# DM2080_Connector_A.net
KiCad netlist of a schematic drawn in Altium Designer
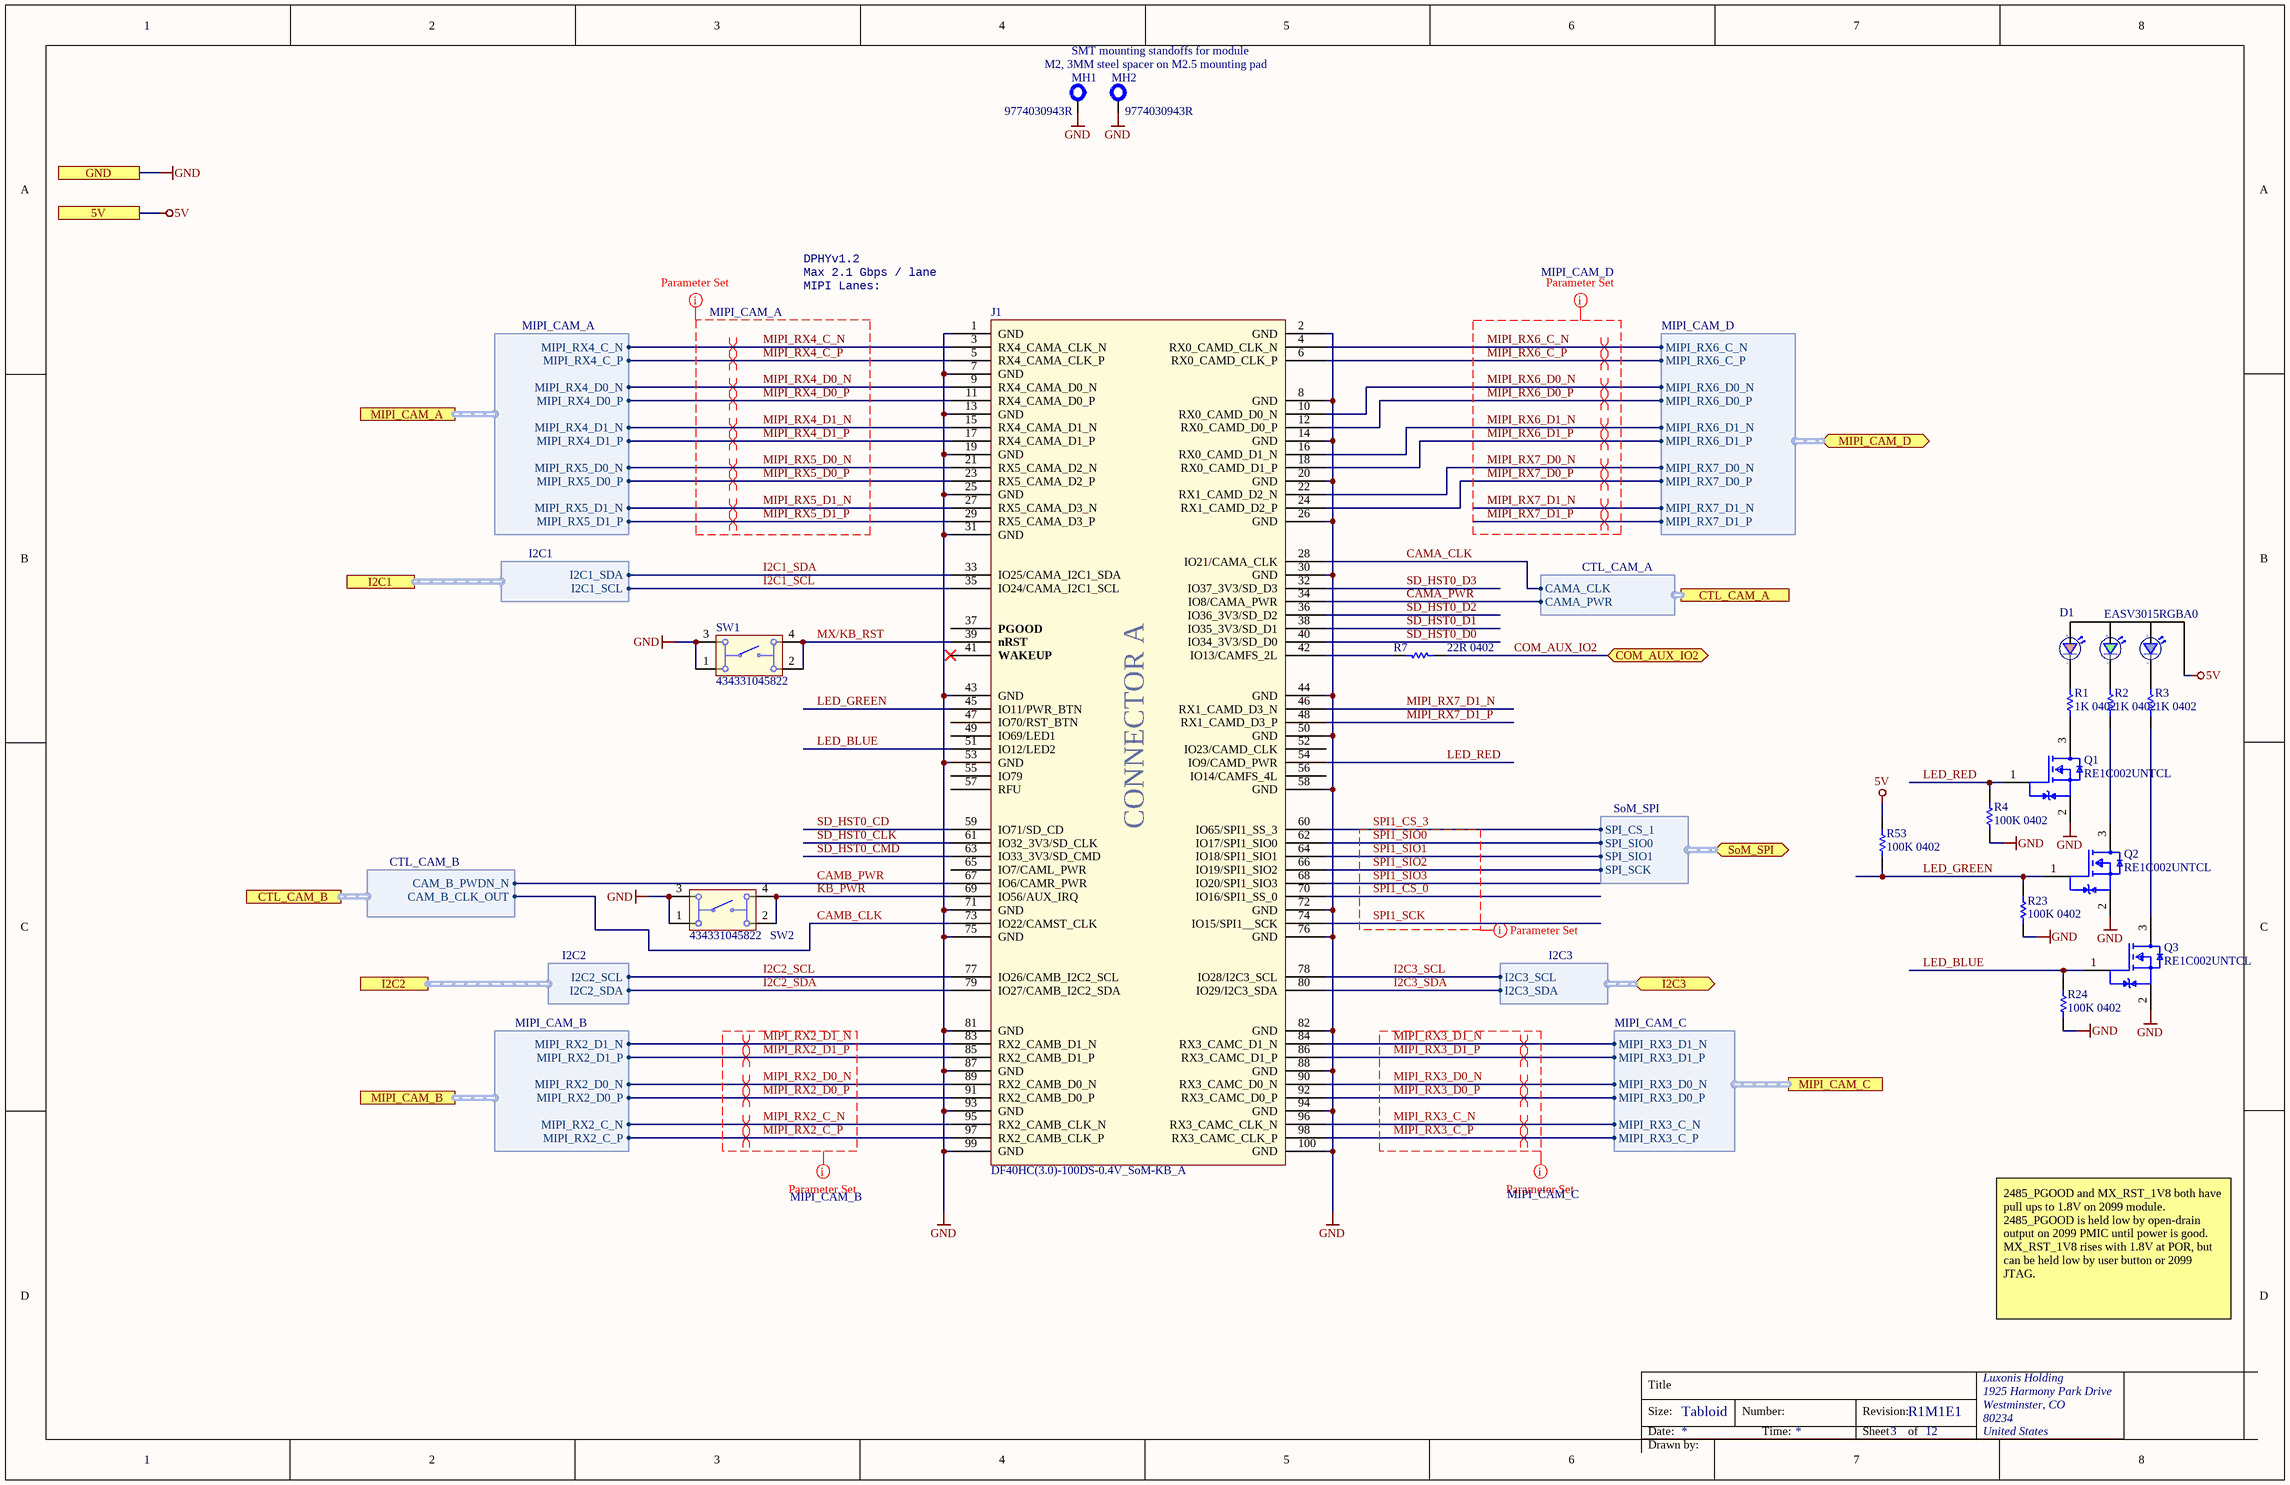
[diagram p0: DM2080_Connector_A.SchDoc]

(export (version "E")
  (design (tool "Eeschema 10.0.6"))
  (components
    (comp (ref "D1")
      (value "EASV3015RGBA0")
      (footprint "EASV3015RGBA0")
      (description "LED Tri-Color Blue/Green/Red 468nm/518nm/632nm 4-Pin SMD")
      (libsource (lib "NG2391C-HM") (part "EASV3015RGBA0"))
    )
    (comp (ref "J1")
      (value "DF40HC(3.0)-100DS-0.4V_SoM-KB_A")
      (footprint "CON_A_SoM-Pro-KB_DF40HC-3.0-100DS-0.4V_minpad")
      (description "OAK-SoM-Pro-S3 base board conn. A")
      (libsource (lib "Luxonis LLC") (part "DF40HC(3.0)-100DS-0.4V_SoM-KB_A"))
    )
    (comp (ref "MH1")
      (value "9774030943R")
      (footprint "9774030943R")
      (description "Spacers/Standoffs")
      (libsource (lib "Luxonis LLC") (part "9774030943R"))
    )
    (comp (ref "MH2")
      (value "9774030943R")
      (footprint "9774030943R")
      (description "Spacers/Standoffs")
      (libsource (lib "Luxonis LLC") (part "9774030943R"))
    )
    (comp (ref "Q1")
      (value "RE1C002UNTCL")
      (footprint "LuxonisMaster:RE1C002UNTCL")
      (description "MOSFET N-CH 20V 0.2A EMT3")
      (libsource (lib "LuxonisMaster") (part "RE1C002UNTCL"))
    )
    (comp (ref "Q2")
      (value "RE1C002UNTCL")
      (footprint "LuxonisMaster:RE1C002UNTCL")
      (description "MOSFET N-CH 20V 0.2A EMT3")
      (libsource (lib "LuxonisMaster") (part "RE1C002UNTCL"))
    )
    (comp (ref "Q3")
      (value "RE1C002UNTCL")
      (footprint "LuxonisMaster:RE1C002UNTCL")
      (description "MOSFET N-CH 20V 0.2A EMT3")
      (libsource (lib "LuxonisMaster") (part "RE1C002UNTCL"))
    )
    (comp (ref "R1")
      (value "1K 0402")
      (footprint "RES_Altium_Vault_Generic:RESC0402(1005)_L")
      (description "RES SMD 1K OHM 1% 1/16W 0402")
      (fields (field (name "TOLERANCE") "1%"))
      (libsource (lib "LuxonisMaster") (part "RC0402FR-071KL"))
    )
    (comp (ref "R2")
      (value "1K 0402")
      (footprint "RES_Altium_Vault_Generic:RESC0402(1005)_L")
      (description "RES SMD 1K OHM 1% 1/16W 0402")
      (fields (field (name "TOLERANCE") "1%"))
      (libsource (lib "LuxonisMaster") (part "RC0402FR-071KL"))
    )
    (comp (ref "R3")
      (value "1K 0402")
      (footprint "RES_Altium_Vault_Generic:RESC0402(1005)_L")
      (description "RES SMD 1K OHM 1% 1/16W 0402")
      (fields (field (name "TOLERANCE") "1%"))
      (libsource (lib "LuxonisMaster") (part "RC0402FR-071KL"))
    )
    (comp (ref "R4")
      (value "100K 0402")
      (footprint "RESC0402(1005)_L")
      (description "RES SMD 100K OHM 1% 1/16W 0402")
      (fields (field (name "TOLERANCE") "1%"))
      (libsource (lib "Luxonis LLC") (part "CR0402-FX-2492GLF"))
    )
    (comp (ref "R7")
      (value "22R 0402")
      (footprint "RES_Altium_Vault_Generic:RESC0402(1005)_L")
      (description "RES SMD 22 OHM 1% 1/16W 0402")
      (fields (field (name "TOLERANCE") "1%"))
      (libsource (lib "BW2098POE") (part "RC0402FR-0722RL"))
    )
    (comp (ref "R23")
      (value "100K 0402")
      (footprint "RESC0402(1005)_L")
      (description "RES SMD 100K OHM 1% 1/16W 0402")
      (fields (field (name "TOLERANCE") "1%"))
      (libsource (lib "Luxonis LLC") (part "CR0402-FX-2492GLF"))
    )
    (comp (ref "R24")
      (value "100K 0402")
      (footprint "RESC0402(1005)_L")
      (description "RES SMD 100K OHM 1% 1/16W 0402")
      (fields (field (name "TOLERANCE") "1%"))
      (libsource (lib "Luxonis LLC") (part "CR0402-FX-2492GLF"))
    )
    (comp (ref "R53")
      (value "100K 0402")
      (footprint "RESC0402(1005)_L")
      (description "RES SMD 100K OHM 1% 1/16W 0402")
      (fields (field (name "TOLERANCE") "1%"))
      (libsource (lib "Luxonis LLC") (part "CR0402-FX-2492GLF"))
    )
    (comp (ref "SW1")
      (value "434331045822")
      (footprint "434331045822")
      (libsource (lib "Luxonis LLC") (part "WE-TACT-SW-4"))
    )
    (comp (ref "SW2")
      (value "434331045822")
      (footprint "434331045822")
      (libsource (lib "Luxonis LLC") (part "WE-TACT-SW-4"))
    )
  )
  (nets
    (net (code "11") (name "/CAMA_CLK") (class "Default")
      (node (ref "J1") (pin "28") (pinfunction "IO21/CAMA_CLK_28") (pintype "passive"))
    )
    (net (code "12") (name "/CAMA_PWR") (class "Default")
      (node (ref "J1") (pin "34") (pinfunction "IO8/CAMA_PWR_34") (pintype "passive"))
    )
    (net (code "13") (name "/CAMB_CLK") (class "Default")
      (node (ref "J1") (pin "73") (pinfunction "IO22/CAMST_CLK_73") (pintype "passive"))
    )
    (net (code "14") (name "/CAMB_PWR") (class "Default")
      (node (ref "J1") (pin "67") (pinfunction "IO6/CAMR_PWR_67") (pintype "passive"))
    )
    (net (code "15") (name "/COM_AUX_IO2") (class "Default")
      (node (ref "R7") (pin "1") (pinfunction "1_1") (pintype "passive"))
    )
    (net (code "16") (name "/I2C1_SCL") (class "Default")
      (node (ref "J1") (pin "35") (pinfunction "IO24/CAMA_I2C1_SCL_35") (pintype "passive"))
    )
    (net (code "17") (name "/I2C1_SDA") (class "Default")
      (node (ref "J1") (pin "33") (pinfunction "IO25/CAMA_I2C1_SDA_33") (pintype "passive"))
    )
    (net (code "18") (name "/I2C2_SCL") (class "Default")
      (node (ref "J1") (pin "77") (pinfunction "IO26/CAMB_I2C2_SCL_77") (pintype "passive"))
    )
    (net (code "19") (name "/I2C2_SDA") (class "Default")
      (node (ref "J1") (pin "79") (pinfunction "IO27/CAMB_I2C2_SDA_79") (pintype "passive"))
    )
    (net (code "20") (name "/I2C3_SCL") (class "Default")
      (node (ref "J1") (pin "78") (pinfunction "IO28/I2C3_SCL_78") (pintype "passive"))
    )
    (net (code "21") (name "/I2C3_SDA") (class "Default")
      (node (ref "J1") (pin "80") (pinfunction "IO29/I2C3_SDA_80") (pintype "passive"))
    )
    (net (code "22") (name "/KB_PWR") (class "Default")
      (node (ref "J1") (pin "69") (pinfunction "IO56/AUX_IRQ_69") (pintype "passive"))
      (node (ref "SW2") (pin "2") (pinfunction "2_2") (pintype "passive"))
      (node (ref "SW2") (pin "4") (pinfunction "4_4") (pintype "passive"))
    )
    (net (code "23") (name "/LED_BLUE") (class "Default")
      (node (ref "J1") (pin "51") (pinfunction "IO12/LED2_51") (pintype "passive"))
      (node (ref "Q3") (pin "1") (pinfunction "Gate_1") (pintype "passive"))
      (node (ref "R24") (pin "1") (pinfunction "1_1") (pintype "passive"))
    )
    (net (code "24") (name "/LED_GREEN") (class "Default")
      (node (ref "J1") (pin "45") (pinfunction "IO11/PWR_BTN_45") (pintype "passive"))
      (node (ref "Q2") (pin "1") (pinfunction "Gate_1") (pintype "passive"))
      (node (ref "R23") (pin "1") (pinfunction "1_1") (pintype "passive"))
      (node (ref "R53") (pin "2") (pinfunction "2_2") (pintype "passive"))
    )
    (net (code "25") (name "/LED_RED") (class "Default")
      (node (ref "J1") (pin "54") (pinfunction "IO9/CAMD_PWR_54") (pintype "passive"))
      (node (ref "Q1") (pin "1") (pinfunction "Gate_1") (pintype "passive"))
      (node (ref "R4") (pin "1") (pinfunction "1_1") (pintype "passive"))
    )
    (net (code "26") (name "/MIPI_RX2_C_N") (class "Default")
      (node (ref "J1") (pin "95") (pinfunction "RX2_CAMB_CLK_N_95") (pintype "passive"))
    )
    (net (code "27") (name "/MIPI_RX2_C_P") (class "Default")
      (node (ref "J1") (pin "97") (pinfunction "RX2_CAMB_CLK_P_97") (pintype "passive"))
    )
    (net (code "28") (name "/MIPI_RX2_D0_N") (class "Default")
      (node (ref "J1") (pin "89") (pinfunction "RX2_CAMB_D0_N_89") (pintype "passive"))
    )
    (net (code "29") (name "/MIPI_RX2_D0_P") (class "Default")
      (node (ref "J1") (pin "91") (pinfunction "RX2_CAMB_D0_P_91") (pintype "passive"))
    )
    (net (code "30") (name "/MIPI_RX2_D1_N") (class "Default")
      (node (ref "J1") (pin "83") (pinfunction "RX2_CAMB_D1_N_83") (pintype "passive"))
    )
    (net (code "31") (name "/MIPI_RX2_D1_P") (class "Default")
      (node (ref "J1") (pin "85") (pinfunction "RX2_CAMB_D1_P_85") (pintype "passive"))
    )
    (net (code "32") (name "/MIPI_RX3_C_N") (class "Default")
      (node (ref "J1") (pin "96") (pinfunction "RX3_CAMC_CLK_N_96") (pintype "passive"))
    )
    (net (code "33") (name "/MIPI_RX3_C_P") (class "Default")
      (node (ref "J1") (pin "98") (pinfunction "RX3_CAMC_CLK_P_98") (pintype "passive"))
    )
    (net (code "34") (name "/MIPI_RX3_D0_N") (class "Default")
      (node (ref "J1") (pin "90") (pinfunction "RX3_CAMC_D0_N_90") (pintype "passive"))
    )
    (net (code "35") (name "/MIPI_RX3_D0_P") (class "Default")
      (node (ref "J1") (pin "92") (pinfunction "RX3_CAMC_D0_P_92") (pintype "passive"))
    )
    (net (code "36") (name "/MIPI_RX3_D1_N") (class "Default")
      (node (ref "J1") (pin "84") (pinfunction "RX3_CAMC_D1_N_84") (pintype "passive"))
    )
    (net (code "37") (name "/MIPI_RX3_D1_P") (class "Default")
      (node (ref "J1") (pin "86") (pinfunction "RX3_CAMC_D1_P_86") (pintype "passive"))
    )
    (net (code "38") (name "/MIPI_RX4_C_N") (class "Default")
      (node (ref "J1") (pin "3") (pinfunction "RX4_CAMA_CLK_N_3") (pintype "passive"))
    )
    (net (code "39") (name "/MIPI_RX4_C_P") (class "Default")
      (node (ref "J1") (pin "5") (pinfunction "RX4_CAMA_CLK_P_5") (pintype "passive"))
    )
    (net (code "40") (name "/MIPI_RX4_D0_N") (class "Default")
      (node (ref "J1") (pin "9") (pinfunction "RX4_CAMA_D0_N_9") (pintype "passive"))
    )
    (net (code "41") (name "/MIPI_RX4_D0_P") (class "Default")
      (node (ref "J1") (pin "11") (pinfunction "RX4_CAMA_D0_P_11") (pintype "passive"))
    )
    (net (code "42") (name "/MIPI_RX4_D1_N") (class "Default")
      (node (ref "J1") (pin "15") (pinfunction "RX4_CAMA_D1_N_15") (pintype "passive"))
    )
    (net (code "43") (name "/MIPI_RX4_D1_P") (class "Default")
      (node (ref "J1") (pin "17") (pinfunction "RX4_CAMA_D1_P_17") (pintype "passive"))
    )
    (net (code "44") (name "/MIPI_RX5_D0_N") (class "Default")
      (node (ref "J1") (pin "21") (pinfunction "RX5_CAMA_D2_N_21") (pintype "passive"))
    )
    (net (code "45") (name "/MIPI_RX5_D0_P") (class "Default")
      (node (ref "J1") (pin "23") (pinfunction "RX5_CAMA_D2_P_23") (pintype "passive"))
    )
    (net (code "46") (name "/MIPI_RX5_D1_N") (class "Default")
      (node (ref "J1") (pin "27") (pinfunction "RX5_CAMA_D3_N_27") (pintype "passive"))
    )
    (net (code "47") (name "/MIPI_RX5_D1_P") (class "Default")
      (node (ref "J1") (pin "29") (pinfunction "RX5_CAMA_D3_P_29") (pintype "passive"))
    )
    (net (code "48") (name "/MIPI_RX6_C_N") (class "Default")
      (node (ref "J1") (pin "4") (pinfunction "RX0_CAMD_CLK_N_4") (pintype "passive"))
    )
    (net (code "49") (name "/MIPI_RX6_C_P") (class "Default")
      (node (ref "J1") (pin "6") (pinfunction "RX0_CAMD_CLK_P_6") (pintype "passive"))
    )
    (net (code "50") (name "/MIPI_RX6_D0_N") (class "Default")
      (node (ref "J1") (pin "10") (pinfunction "RX0_CAMD_D0_N_10") (pintype "passive"))
    )
    (net (code "51") (name "/MIPI_RX6_D0_P") (class "Default")
      (node (ref "J1") (pin "12") (pinfunction "RX0_CAMD_D0_P_12") (pintype "passive"))
    )
    (net (code "52") (name "/MIPI_RX6_D1_N") (class "Default")
      (node (ref "J1") (pin "16") (pinfunction "RX0_CAMD_D1_N_16") (pintype "passive"))
    )
    (net (code "53") (name "/MIPI_RX6_D1_P") (class "Default")
      (node (ref "J1") (pin "18") (pinfunction "RX0_CAMD_D1_P_18") (pintype "passive"))
    )
    (net (code "54") (name "/MIPI_RX7_D0_N") (class "Default")
      (node (ref "J1") (pin "22") (pinfunction "RX1_CAMD_D2_N_22") (pintype "passive"))
    )
    (net (code "55") (name "/MIPI_RX7_D0_P") (class "Default")
      (node (ref "J1") (pin "24") (pinfunction "RX1_CAMD_D2_P_24") (pintype "passive"))
    )
    (net (code "56") (name "/MIPI_RX7_D1_N") (class "Default")
      (node (ref "J1") (pin "46") (pinfunction "RX1_CAMD_D3_N_46") (pintype "passive"))
    )
    (net (code "57") (name "/MIPI_RX7_D1_P") (class "Default")
      (node (ref "J1") (pin "48") (pinfunction "RX1_CAMD_D3_P_48") (pintype "passive"))
    )
    (net (code "58") (name "/MX{slash}KB_RST") (class "Default")
      (node (ref "J1") (pin "39") (pinfunction "nRST_39") (pintype "passive"))
      (node (ref "SW1") (pin "2") (pinfunction "2_2") (pintype "passive"))
      (node (ref "SW1") (pin "4") (pinfunction "4_4") (pintype "passive"))
    )
    (net (code "59") (name "/SD_HST0_CD") (class "Default")
      (node (ref "J1") (pin "59") (pinfunction "IO71/SD_CD_59") (pintype "passive"))
    )
    (net (code "60") (name "/SD_HST0_CLK") (class "Default")
      (node (ref "J1") (pin "61") (pinfunction "IO32_3V3/SD_CLK_61") (pintype "passive"))
    )
    (net (code "61") (name "/SD_HST0_CMD") (class "Default")
      (node (ref "J1") (pin "63") (pinfunction "IO33_3V3/SD_CMD_63") (pintype "passive"))
    )
    (net (code "62") (name "/SD_HST0_D0") (class "Default")
      (node (ref "J1") (pin "40") (pinfunction "IO34_3V3/SD_D0_40") (pintype "passive"))
    )
    (net (code "63") (name "/SD_HST0_D1") (class "Default")
      (node (ref "J1") (pin "38") (pinfunction "IO35_3V3/SD_D1_38") (pintype "passive"))
    )
    (net (code "64") (name "/SD_HST0_D2") (class "Default")
      (node (ref "J1") (pin "36") (pinfunction "IO36_3V3/SD_D2_36") (pintype "passive"))
    )
    (net (code "65") (name "/SD_HST0_D3") (class "Default")
      (node (ref "J1") (pin "32") (pinfunction "IO37_3V3/SD_D3_32") (pintype "passive"))
    )
    (net (code "66") (name "/SPI1_CS_0") (class "Default")
      (node (ref "J1") (pin "70") (pinfunction "IO16/SPI1_SS_0_70") (pintype "passive"))
    )
    (net (code "67") (name "/SPI1_CS_3") (class "Default")
      (node (ref "J1") (pin "60") (pinfunction "IO65/SPI1_SS_3_60") (pintype "passive"))
    )
    (net (code "68") (name "/SPI1_SCK") (class "Default")
      (node (ref "J1") (pin "74") (pinfunction "IO15/SPI1__SCK_74") (pintype "passive"))
    )
    (net (code "69") (name "/SPI1_SIO0") (class "Default")
      (node (ref "J1") (pin "62") (pinfunction "IO17/SPI1_SIO0_62") (pintype "passive"))
    )
    (net (code "70") (name "/SPI1_SIO1") (class "Default")
      (node (ref "J1") (pin "64") (pinfunction "IO18/SPI1_SIO1_64") (pintype "passive"))
    )
    (net (code "71") (name "/SPI1_SIO2") (class "Default")
      (node (ref "J1") (pin "66") (pinfunction "IO19/SPI1_SIO2_66") (pintype "passive"))
    )
    (net (code "72") (name "/SPI1_SIO3") (class "Default")
      (node (ref "J1") (pin "68") (pinfunction "IO20/SPI1_SIO3_68") (pintype "passive"))
    )
    (net (code "83") (name "5V") (class "Default")
      (node (ref "D1") (pin "1") (pinfunction "A_1") (pintype "passive"))
      (node (ref "R53") (pin "1") (pinfunction "1_1") (pintype "passive"))
    )
    (net (code "84") (name "GND") (class "Default")
      (node (ref "J1") (pin "1") (pinfunction "GND_1") (pintype "passive"))
      (node (ref "J1") (pin "100") (pinfunction "GND_100") (pintype "passive"))
      (node (ref "J1") (pin "13") (pinfunction "GND_13") (pintype "passive"))
      (node (ref "J1") (pin "14") (pinfunction "GND_14") (pintype "passive"))
      (node (ref "J1") (pin "19") (pinfunction "GND_19") (pintype "passive"))
      (node (ref "J1") (pin "2") (pinfunction "GND_2") (pintype "passive"))
      (node (ref "J1") (pin "20") (pinfunction "GND_20") (pintype "passive"))
      (node (ref "J1") (pin "25") (pinfunction "GND_25") (pintype "passive"))
      (node (ref "J1") (pin "26") (pinfunction "GND_26") (pintype "passive"))
      (node (ref "J1") (pin "30") (pinfunction "GND_30") (pintype "passive"))
      (node (ref "J1") (pin "31") (pinfunction "GND_31") (pintype "passive"))
      (node (ref "J1") (pin "43") (pinfunction "GND_43") (pintype "passive"))
      (node (ref "J1") (pin "44") (pinfunction "GND_44") (pintype "passive"))
      (node (ref "J1") (pin "50") (pinfunction "GND_50") (pintype "passive"))
      (node (ref "J1") (pin "53") (pinfunction "GND_53") (pintype "passive"))
      (node (ref "J1") (pin "58") (pinfunction "GND_58") (pintype "passive"))
      (node (ref "J1") (pin "7") (pinfunction "GND_7") (pintype "passive"))
      (node (ref "J1") (pin "71") (pinfunction "GND_71") (pintype "passive"))
      (node (ref "J1") (pin "72") (pinfunction "GND_72") (pintype "passive"))
      (node (ref "J1") (pin "75") (pinfunction "GND_75") (pintype "passive"))
      (node (ref "J1") (pin "76") (pinfunction "GND_76") (pintype "passive"))
      (node (ref "J1") (pin "8") (pinfunction "GND_8") (pintype "passive"))
      (node (ref "J1") (pin "81") (pinfunction "GND_81") (pintype "passive"))
      (node (ref "J1") (pin "82") (pinfunction "GND_82") (pintype "passive"))
      (node (ref "J1") (pin "87") (pinfunction "GND_87") (pintype "passive"))
      (node (ref "J1") (pin "88") (pinfunction "GND_88") (pintype "passive"))
      (node (ref "J1") (pin "93") (pinfunction "GND_93") (pintype "passive"))
      (node (ref "J1") (pin "94") (pinfunction "GND_94") (pintype "passive"))
      (node (ref "J1") (pin "99") (pinfunction "GND_99") (pintype "passive"))
      (node (ref "MH1") (pin "1") (pintype "passive"))
      (node (ref "MH2") (pin "1") (pintype "passive"))
      (node (ref "Q1") (pin "2") (pinfunction "Source_2") (pintype "passive"))
      (node (ref "Q2") (pin "2") (pinfunction "Source_2") (pintype "passive"))
      (node (ref "Q3") (pin "2") (pinfunction "Source_2") (pintype "passive"))
      (node (ref "R23") (pin "2") (pinfunction "2_2") (pintype "passive"))
      (node (ref "R24") (pin "2") (pinfunction "2_2") (pintype "passive"))
      (node (ref "R4") (pin "2") (pinfunction "2_2") (pintype "passive"))
      (node (ref "SW1") (pin "1") (pinfunction "1_1") (pintype "passive"))
      (node (ref "SW1") (pin "3") (pinfunction "3_3") (pintype "passive"))
      (node (ref "SW2") (pin "1") (pinfunction "1_1") (pintype "passive"))
      (node (ref "SW2") (pin "3") (pinfunction "3_3") (pintype "passive"))
    )
    (net (code "85") (name "Net-(D1-C-Pad2)") (class "Default")
      (node (ref "D1") (pin "2") (pinfunction "C_2") (pintype "passive"))
      (node (ref "R3") (pin "2") (pinfunction "2_2") (pintype "passive"))
    )
    (net (code "86") (name "Net-(D1-C-Pad3)") (class "Default")
      (node (ref "D1") (pin "3") (pinfunction "C_3") (pintype "passive"))
      (node (ref "R2") (pin "2") (pinfunction "2_2") (pintype "passive"))
    )
    (net (code "87") (name "Net-(D1-C-Pad4)") (class "Default")
      (node (ref "D1") (pin "4") (pinfunction "C_4") (pintype "passive"))
      (node (ref "R1") (pin "2") (pinfunction "2_2") (pintype "passive"))
    )
    (net (code "88") (name "Net-(J1-IO13{slash}CAMFS_2L)") (class "Default")
      (node (ref "J1") (pin "42") (pinfunction "IO13/CAMFS_2L_42") (pintype "passive"))
      (node (ref "R7") (pin "2") (pinfunction "2_2") (pintype "passive"))
    )
    (net (code "89") (name "Net-(Q1-Drain)") (class "Default")
      (node (ref "Q1") (pin "3") (pinfunction "Drain_3") (pintype "passive"))
      (node (ref "R1") (pin "1") (pinfunction "1_1") (pintype "passive"))
    )
    (net (code "90") (name "Net-(Q2-Drain)") (class "Default")
      (node (ref "Q2") (pin "3") (pinfunction "Drain_3") (pintype "passive"))
      (node (ref "R2") (pin "1") (pinfunction "1_1") (pintype "passive"))
    )
    (net (code "91") (name "Net-(Q3-Drain)") (class "Default")
      (node (ref "Q3") (pin "3") (pinfunction "Drain_3") (pintype "passive"))
      (node (ref "R3") (pin "1") (pinfunction "1_1") (pintype "passive"))
    )
    (net (code "92") (name "unconnected-(J1-IO7{slash}CAML_PWR-Pad65)") (class "Default")
      (node (ref "J1") (pin "65") (pinfunction "IO7/CAML_PWR_65") (pintype "passive"))
    )
    (net (code "93") (name "unconnected-(J1-IO14{slash}CAMFS_4L-Pad56)") (class "Default")
      (node (ref "J1") (pin "56") (pinfunction "IO14/CAMFS_4L_56") (pintype "passive"))
    )
    (net (code "94") (name "unconnected-(J1-IO23{slash}CAMD_CLK-Pad52)") (class "Default")
      (node (ref "J1") (pin "52") (pinfunction "IO23/CAMD_CLK_52") (pintype "passive"))
    )
    (net (code "95") (name "unconnected-(J1-IO69{slash}LED1-Pad49)") (class "Default")
      (node (ref "J1") (pin "49") (pinfunction "IO69/LED1_49") (pintype "passive"))
    )
    (net (code "96") (name "unconnected-(J1-IO70{slash}RST_BTN-Pad47)") (class "Default")
      (node (ref "J1") (pin "47") (pinfunction "IO70/RST_BTN_47") (pintype "passive"))
    )
    (net (code "97") (name "unconnected-(J1-IO79-Pad55)") (class "Default")
      (node (ref "J1") (pin "55") (pinfunction "IO79_55") (pintype "passive"))
    )
    (net (code "98") (name "unconnected-(J1-PGOOD-Pad37)") (class "Default")
      (node (ref "J1") (pin "37") (pinfunction "PGOOD_37") (pintype "passive"))
    )
    (net (code "99") (name "unconnected-(J1-RFU-Pad57)") (class "Default")
      (node (ref "J1") (pin "57") (pinfunction "RFU_57") (pintype "passive"))
    )
    (net (code "100") (name "unconnected-(J1-WAKEUP-Pad41)") (class "Default")
      (node (ref "J1") (pin "41") (pinfunction "WAKEUP_41") (pintype "passive+no_connect"))
    )
  )
)
